# H851X.net
KiCad netlist of a schematic drawn in EAGLE
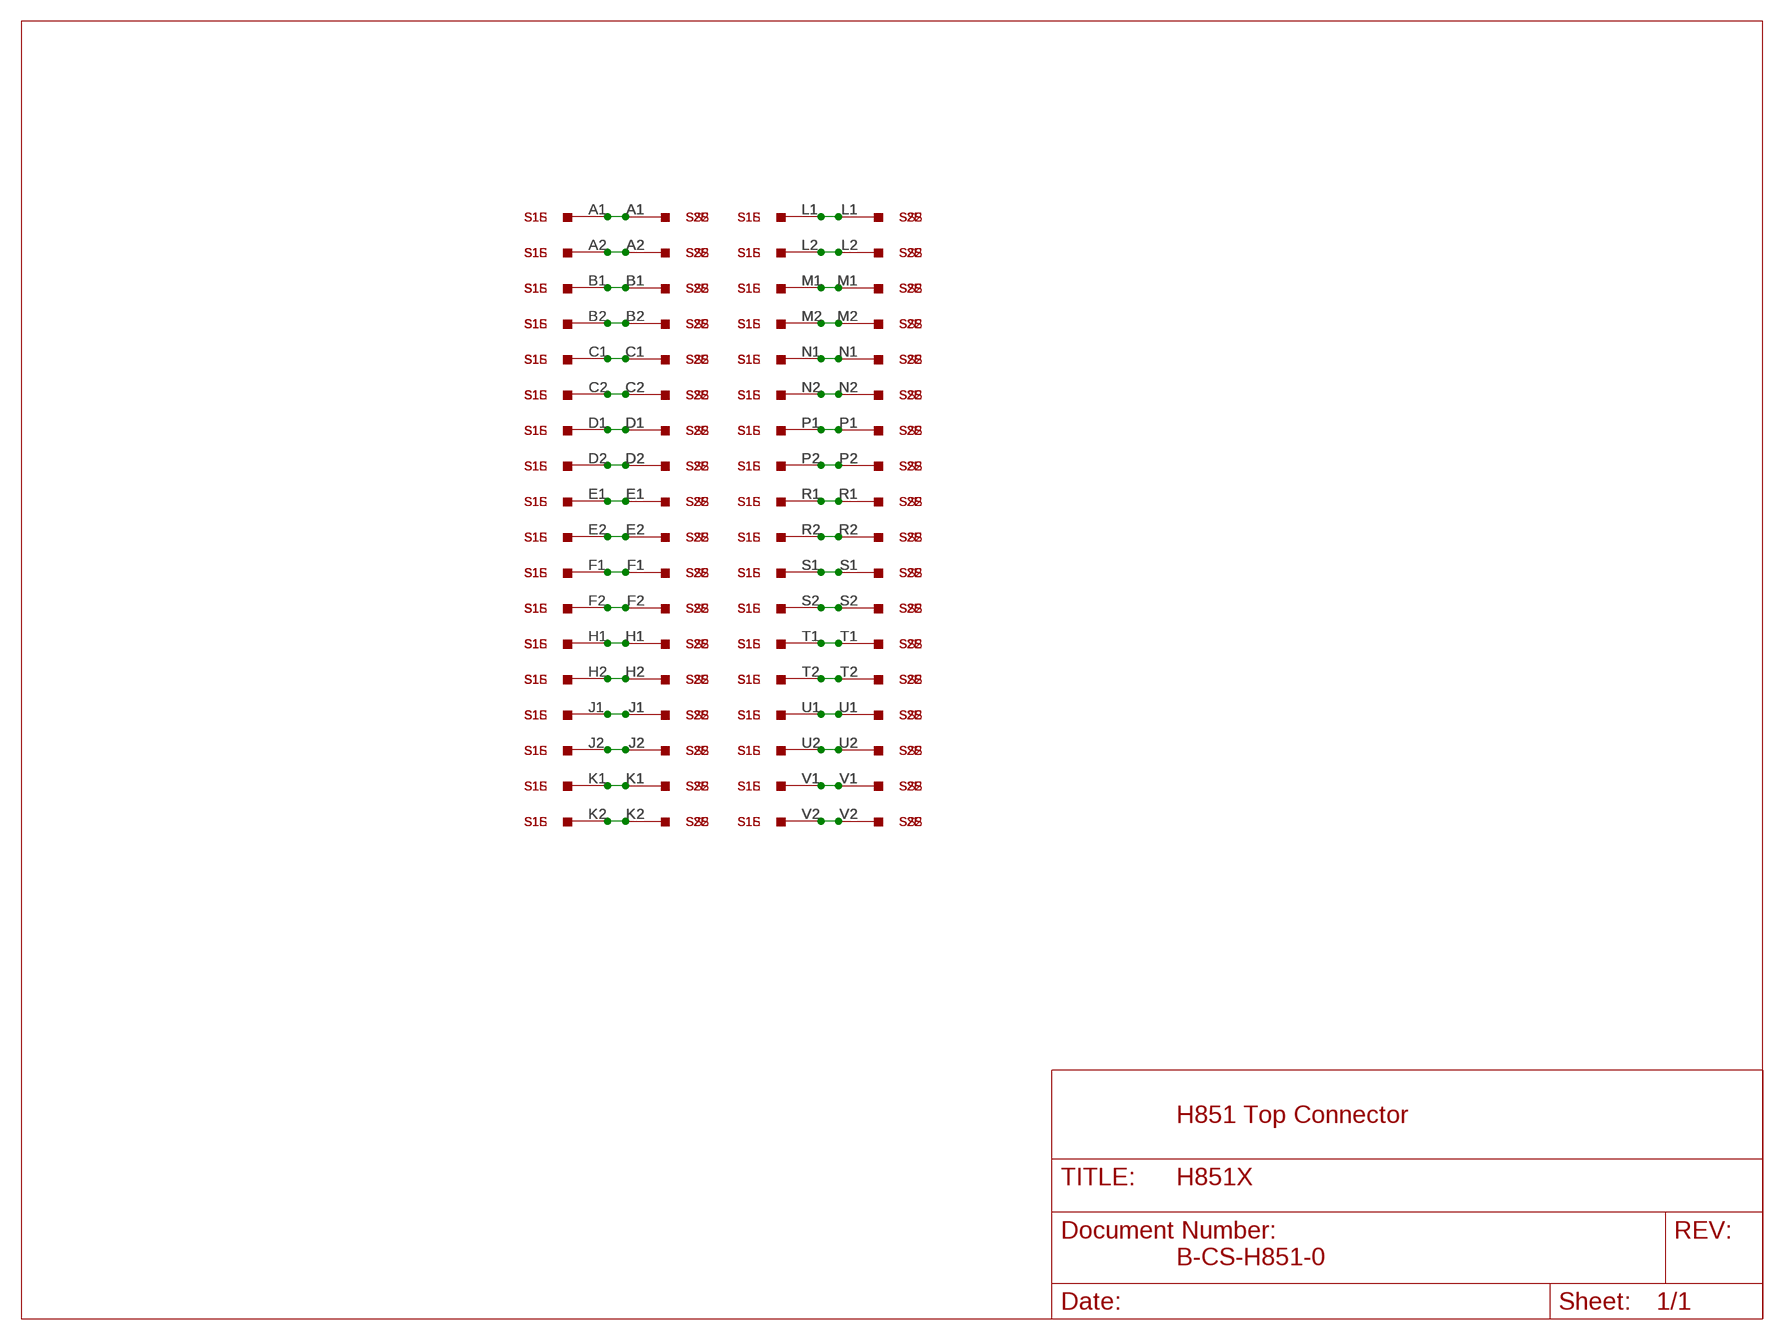
[diagram p0: schematic, sheet 1]

(export (version "E")
  (design (tool "Eeschema 10.0.6"))
  (components
    (comp (ref "S1")
      (value "M916")
      (footprint "eagle-import:H807")
      (libsource (lib "eagle-import") (part "M916"))
    )
    (comp (ref "S1E")
      (value "M916EDAC")
      (footprint "eagle-import:EDAC346-36")
      (libsource (lib "eagle-import") (part "M916EDAC"))
    )
    (comp (ref "S1S")
      (value "M916ECS")
      (footprint "eagle-import:ECS2418")
      (libsource (lib "eagle-import") (part "M916ECS"))
    )
    (comp (ref "S2")
      (value "M916")
      (footprint "eagle-import:H807")
      (libsource (lib "eagle-import") (part "M916"))
    )
    (comp (ref "S2E")
      (value "M916EDAC")
      (footprint "eagle-import:EDAC346-36")
      (libsource (lib "eagle-import") (part "M916EDAC"))
    )
    (comp (ref "S2S")
      (value "M916ECS")
      (footprint "eagle-import:ECS2418")
      (libsource (lib "eagle-import") (part "M916ECS"))
    )
  )
  (nets
    (net (code "1") (name "Net-(S1A-P$2)") (class "Default")
      (node (ref "S1") (pin "A1") (pinfunction "P$2_A1") (pintype "bidirectional"))
      (node (ref "S1E") (pin "A1") (pinfunction "P$2_A1") (pintype "bidirectional"))
      (node (ref "S1S") (pin "A1") (pinfunction "P$2_A1") (pintype "bidirectional"))
      (node (ref "S2") (pin "A1") (pinfunction "P$2_A1") (pintype "bidirectional"))
      (node (ref "S2E") (pin "A1") (pinfunction "P$2_A1") (pintype "bidirectional"))
      (node (ref "S2S") (pin "A1") (pinfunction "P$2_A1") (pintype "bidirectional"))
    )
    (net (code "2") (name "Net-(S1AA-P$2)") (class "Default")
      (node (ref "S1") (pin "R1") (pinfunction "P$2_R1") (pintype "bidirectional"))
      (node (ref "S1E") (pin "R1") (pinfunction "P$2_R1") (pintype "bidirectional"))
      (node (ref "S1S") (pin "R1") (pinfunction "P$2_R1") (pintype "bidirectional"))
      (node (ref "S2") (pin "R1") (pinfunction "P$2_R1") (pintype "bidirectional"))
      (node (ref "S2E") (pin "R1") (pinfunction "P$2_R1") (pintype "bidirectional"))
      (node (ref "S2S") (pin "R1") (pinfunction "P$2_R1") (pintype "bidirectional"))
    )
    (net (code "3") (name "Net-(S1AB-P$2)") (class "Default")
      (node (ref "S1") (pin "R2") (pinfunction "P$2_R2") (pintype "bidirectional"))
      (node (ref "S1E") (pin "R2") (pinfunction "P$2_R2") (pintype "bidirectional"))
      (node (ref "S1S") (pin "R2") (pinfunction "P$2_R2") (pintype "bidirectional"))
      (node (ref "S2") (pin "R2") (pinfunction "P$2_R2") (pintype "bidirectional"))
      (node (ref "S2E") (pin "R2") (pinfunction "P$2_R2") (pintype "bidirectional"))
      (node (ref "S2S") (pin "R2") (pinfunction "P$2_R2") (pintype "bidirectional"))
    )
    (net (code "4") (name "Net-(S1AC-P$2)") (class "Default")
      (node (ref "S1") (pin "S1") (pinfunction "P$2_S1") (pintype "bidirectional"))
      (node (ref "S1E") (pin "S1") (pinfunction "P$2_S1") (pintype "bidirectional"))
      (node (ref "S1S") (pin "S1") (pinfunction "P$2_S1") (pintype "bidirectional"))
      (node (ref "S2") (pin "S1") (pinfunction "P$2_S1") (pintype "bidirectional"))
      (node (ref "S2E") (pin "S1") (pinfunction "P$2_S1") (pintype "bidirectional"))
      (node (ref "S2S") (pin "S1") (pinfunction "P$2_S1") (pintype "bidirectional"))
    )
    (net (code "5") (name "Net-(S1AD-P$2)") (class "Default")
      (node (ref "S1") (pin "S2") (pinfunction "P$2_S2") (pintype "bidirectional"))
      (node (ref "S1E") (pin "S2") (pinfunction "P$2_S2") (pintype "bidirectional"))
      (node (ref "S1S") (pin "S2") (pinfunction "P$2_S2") (pintype "bidirectional"))
      (node (ref "S2") (pin "S2") (pinfunction "P$2_S2") (pintype "bidirectional"))
      (node (ref "S2E") (pin "S2") (pinfunction "P$2_S2") (pintype "bidirectional"))
      (node (ref "S2S") (pin "S2") (pinfunction "P$2_S2") (pintype "bidirectional"))
    )
    (net (code "6") (name "Net-(S1AE-P$2)") (class "Default")
      (node (ref "S1") (pin "T1") (pinfunction "P$2_T1") (pintype "bidirectional"))
      (node (ref "S1E") (pin "T1") (pinfunction "P$2_T1") (pintype "bidirectional"))
      (node (ref "S1S") (pin "T1") (pinfunction "P$2_T1") (pintype "bidirectional"))
      (node (ref "S2") (pin "T1") (pinfunction "P$2_T1") (pintype "bidirectional"))
      (node (ref "S2E") (pin "T1") (pinfunction "P$2_T1") (pintype "bidirectional"))
      (node (ref "S2S") (pin "T1") (pinfunction "P$2_T1") (pintype "bidirectional"))
    )
    (net (code "7") (name "Net-(S1AF-P$2)") (class "Default")
      (node (ref "S1") (pin "T2") (pinfunction "P$2_T2") (pintype "bidirectional"))
      (node (ref "S1E") (pin "T2") (pinfunction "P$2_T2") (pintype "bidirectional"))
      (node (ref "S1S") (pin "T2") (pinfunction "P$2_T2") (pintype "bidirectional"))
      (node (ref "S2") (pin "T2") (pinfunction "P$2_T2") (pintype "bidirectional"))
      (node (ref "S2E") (pin "T2") (pinfunction "P$2_T2") (pintype "bidirectional"))
      (node (ref "S2S") (pin "T2") (pinfunction "P$2_T2") (pintype "bidirectional"))
    )
    (net (code "8") (name "Net-(S1AG-P$2)") (class "Default")
      (node (ref "S1") (pin "U1") (pinfunction "P$2_U1") (pintype "bidirectional"))
      (node (ref "S1E") (pin "U1") (pinfunction "P$2_U1") (pintype "bidirectional"))
      (node (ref "S1S") (pin "U1") (pinfunction "P$2_U1") (pintype "bidirectional"))
      (node (ref "S2") (pin "U1") (pinfunction "P$2_U1") (pintype "bidirectional"))
      (node (ref "S2E") (pin "U1") (pinfunction "P$2_U1") (pintype "bidirectional"))
      (node (ref "S2S") (pin "U1") (pinfunction "P$2_U1") (pintype "bidirectional"))
    )
    (net (code "9") (name "Net-(S1AH-P$2)") (class "Default")
      (node (ref "S1") (pin "U2") (pinfunction "P$2_U2") (pintype "bidirectional"))
      (node (ref "S1E") (pin "U2") (pinfunction "P$2_U2") (pintype "bidirectional"))
      (node (ref "S1S") (pin "U2") (pinfunction "P$2_U2") (pintype "bidirectional"))
      (node (ref "S2") (pin "U2") (pinfunction "P$2_U2") (pintype "bidirectional"))
      (node (ref "S2E") (pin "U2") (pinfunction "P$2_U2") (pintype "bidirectional"))
      (node (ref "S2S") (pin "U2") (pinfunction "P$2_U2") (pintype "bidirectional"))
    )
    (net (code "10") (name "Net-(S1AI-P$2)") (class "Default")
      (node (ref "S1") (pin "V1") (pinfunction "P$2_V1") (pintype "bidirectional"))
      (node (ref "S1E") (pin "V1") (pinfunction "P$2_V1") (pintype "bidirectional"))
      (node (ref "S1S") (pin "V1") (pinfunction "P$2_V1") (pintype "bidirectional"))
      (node (ref "S2") (pin "V1") (pinfunction "P$2_V1") (pintype "bidirectional"))
      (node (ref "S2E") (pin "V1") (pinfunction "P$2_V1") (pintype "bidirectional"))
      (node (ref "S2S") (pin "V1") (pinfunction "P$2_V1") (pintype "bidirectional"))
    )
    (net (code "11") (name "Net-(S1AJ-P$2)") (class "Default")
      (node (ref "S1") (pin "V2") (pinfunction "P$2_V2") (pintype "bidirectional"))
      (node (ref "S1E") (pin "V2") (pinfunction "P$2_V2") (pintype "bidirectional"))
      (node (ref "S1S") (pin "V2") (pinfunction "P$2_V2") (pintype "bidirectional"))
      (node (ref "S2") (pin "V2") (pinfunction "P$2_V2") (pintype "bidirectional"))
      (node (ref "S2E") (pin "V2") (pinfunction "P$2_V2") (pintype "bidirectional"))
      (node (ref "S2S") (pin "V2") (pinfunction "P$2_V2") (pintype "bidirectional"))
    )
    (net (code "12") (name "Net-(S1B-P$2)") (class "Default")
      (node (ref "S1") (pin "A2") (pinfunction "P$2_A2") (pintype "bidirectional"))
      (node (ref "S1E") (pin "A2") (pinfunction "P$2_A2") (pintype "bidirectional"))
      (node (ref "S1S") (pin "A2") (pinfunction "P$2_A2") (pintype "bidirectional"))
      (node (ref "S2") (pin "A2") (pinfunction "P$2_A2") (pintype "bidirectional"))
      (node (ref "S2E") (pin "A2") (pinfunction "P$2_A2") (pintype "bidirectional"))
      (node (ref "S2S") (pin "A2") (pinfunction "P$2_A2") (pintype "bidirectional"))
    )
    (net (code "13") (name "Net-(S1C-P$2)") (class "Default")
      (node (ref "S1") (pin "B1") (pinfunction "P$2_B1") (pintype "bidirectional"))
      (node (ref "S1E") (pin "B1") (pinfunction "P$2_B1") (pintype "bidirectional"))
      (node (ref "S1S") (pin "B1") (pinfunction "P$2_B1") (pintype "bidirectional"))
      (node (ref "S2") (pin "B1") (pinfunction "P$2_B1") (pintype "bidirectional"))
      (node (ref "S2E") (pin "B1") (pinfunction "P$2_B1") (pintype "bidirectional"))
      (node (ref "S2S") (pin "B1") (pinfunction "P$2_B1") (pintype "bidirectional"))
    )
    (net (code "14") (name "Net-(S1D-P$2)") (class "Default")
      (node (ref "S1") (pin "B2") (pinfunction "P$2_B2") (pintype "bidirectional"))
      (node (ref "S1E") (pin "B2") (pinfunction "P$2_B2") (pintype "bidirectional"))
      (node (ref "S1S") (pin "B2") (pinfunction "P$2_B2") (pintype "bidirectional"))
      (node (ref "S2") (pin "B2") (pinfunction "P$2_B2") (pintype "bidirectional"))
      (node (ref "S2E") (pin "B2") (pinfunction "P$2_B2") (pintype "bidirectional"))
      (node (ref "S2S") (pin "B2") (pinfunction "P$2_B2") (pintype "bidirectional"))
    )
    (net (code "15") (name "Net-(S1E-P$2)") (class "Default")
      (node (ref "S1") (pin "C1") (pinfunction "P$2_C1") (pintype "bidirectional"))
      (node (ref "S1E") (pin "C1") (pinfunction "P$2_C1") (pintype "bidirectional"))
      (node (ref "S1S") (pin "C1") (pinfunction "P$2_C1") (pintype "bidirectional"))
      (node (ref "S2") (pin "C1") (pinfunction "P$2_C1") (pintype "bidirectional"))
      (node (ref "S2E") (pin "C1") (pinfunction "P$2_C1") (pintype "bidirectional"))
      (node (ref "S2S") (pin "C1") (pinfunction "P$2_C1") (pintype "bidirectional"))
    )
    (net (code "16") (name "Net-(S1EF-P$2)") (class "Default")
      (node (ref "S1") (pin "C2") (pinfunction "P$2_C2") (pintype "bidirectional"))
      (node (ref "S1E") (pin "C2") (pinfunction "P$2_C2") (pintype "bidirectional"))
      (node (ref "S1S") (pin "C2") (pinfunction "P$2_C2") (pintype "bidirectional"))
      (node (ref "S2") (pin "C2") (pinfunction "P$2_C2") (pintype "bidirectional"))
      (node (ref "S2E") (pin "C2") (pinfunction "P$2_C2") (pintype "bidirectional"))
      (node (ref "S2S") (pin "C2") (pinfunction "P$2_C2") (pintype "bidirectional"))
    )
    (net (code "17") (name "Net-(S1EG-P$2)") (class "Default")
      (node (ref "S1") (pin "D1") (pinfunction "P$2_D1") (pintype "bidirectional"))
      (node (ref "S1E") (pin "D1") (pinfunction "P$2_D1") (pintype "bidirectional"))
      (node (ref "S1S") (pin "D1") (pinfunction "P$2_D1") (pintype "bidirectional"))
      (node (ref "S2") (pin "D1") (pinfunction "P$2_D1") (pintype "bidirectional"))
      (node (ref "S2E") (pin "D1") (pinfunction "P$2_D1") (pintype "bidirectional"))
      (node (ref "S2S") (pin "D1") (pinfunction "P$2_D1") (pintype "bidirectional"))
    )
    (net (code "18") (name "Net-(S1EH-P$2)") (class "Default")
      (node (ref "S1") (pin "D2") (pinfunction "P$2_D2") (pintype "bidirectional"))
      (node (ref "S1E") (pin "D2") (pinfunction "P$2_D2") (pintype "bidirectional"))
      (node (ref "S1S") (pin "D2") (pinfunction "P$2_D2") (pintype "bidirectional"))
      (node (ref "S2") (pin "D2") (pinfunction "P$2_D2") (pintype "bidirectional"))
      (node (ref "S2E") (pin "D2") (pinfunction "P$2_D2") (pintype "bidirectional"))
      (node (ref "S2S") (pin "D2") (pinfunction "P$2_D2") (pintype "bidirectional"))
    )
    (net (code "19") (name "Net-(S1EI-P$2)") (class "Default")
      (node (ref "S1") (pin "E1") (pinfunction "P$2_E1") (pintype "bidirectional"))
      (node (ref "S1E") (pin "E1") (pinfunction "P$2_E1") (pintype "bidirectional"))
      (node (ref "S1S") (pin "E1") (pinfunction "P$2_E1") (pintype "bidirectional"))
      (node (ref "S2") (pin "E1") (pinfunction "P$2_E1") (pintype "bidirectional"))
      (node (ref "S2E") (pin "E1") (pinfunction "P$2_E1") (pintype "bidirectional"))
      (node (ref "S2S") (pin "E1") (pinfunction "P$2_E1") (pintype "bidirectional"))
    )
    (net (code "20") (name "Net-(S1EJ-P$2)") (class "Default")
      (node (ref "S1") (pin "E2") (pinfunction "P$2_E2") (pintype "bidirectional"))
      (node (ref "S1E") (pin "E2") (pinfunction "P$2_E2") (pintype "bidirectional"))
      (node (ref "S1S") (pin "E2") (pinfunction "P$2_E2") (pintype "bidirectional"))
      (node (ref "S2") (pin "E2") (pinfunction "P$2_E2") (pintype "bidirectional"))
      (node (ref "S2E") (pin "E2") (pinfunction "P$2_E2") (pintype "bidirectional"))
      (node (ref "S2S") (pin "E2") (pinfunction "P$2_E2") (pintype "bidirectional"))
    )
    (net (code "21") (name "Net-(S1EK-P$2)") (class "Default")
      (node (ref "S1") (pin "F1") (pinfunction "P$2_F1") (pintype "bidirectional"))
      (node (ref "S1E") (pin "F1") (pinfunction "P$2_F1") (pintype "bidirectional"))
      (node (ref "S1S") (pin "F1") (pinfunction "P$2_F1") (pintype "bidirectional"))
      (node (ref "S2") (pin "F1") (pinfunction "P$2_F1") (pintype "bidirectional"))
      (node (ref "S2E") (pin "F1") (pinfunction "P$2_F1") (pintype "bidirectional"))
      (node (ref "S2S") (pin "F1") (pinfunction "P$2_F1") (pintype "bidirectional"))
    )
    (net (code "22") (name "Net-(S1EL-P$2)") (class "Default")
      (node (ref "S1") (pin "F2") (pinfunction "P$2_F2") (pintype "bidirectional"))
      (node (ref "S1E") (pin "F2") (pinfunction "P$2_F2") (pintype "bidirectional"))
      (node (ref "S1S") (pin "F2") (pinfunction "P$2_F2") (pintype "bidirectional"))
      (node (ref "S2") (pin "F2") (pinfunction "P$2_F2") (pintype "bidirectional"))
      (node (ref "S2E") (pin "F2") (pinfunction "P$2_F2") (pintype "bidirectional"))
      (node (ref "S2S") (pin "F2") (pinfunction "P$2_F2") (pintype "bidirectional"))
    )
    (net (code "23") (name "Net-(S1EM-P$2)") (class "Default")
      (node (ref "S1") (pin "H1") (pinfunction "P$2_H1") (pintype "bidirectional"))
      (node (ref "S1E") (pin "H1") (pinfunction "P$2_H1") (pintype "bidirectional"))
      (node (ref "S1S") (pin "H1") (pinfunction "P$2_H1") (pintype "bidirectional"))
      (node (ref "S2") (pin "H1") (pinfunction "P$2_H1") (pintype "bidirectional"))
      (node (ref "S2E") (pin "H1") (pinfunction "P$2_H1") (pintype "bidirectional"))
      (node (ref "S2S") (pin "H1") (pinfunction "P$2_H1") (pintype "bidirectional"))
    )
    (net (code "24") (name "Net-(S1EN-P$2)") (class "Default")
      (node (ref "S1") (pin "H2") (pinfunction "P$2_H2") (pintype "bidirectional"))
      (node (ref "S1E") (pin "H2") (pinfunction "P$2_H2") (pintype "bidirectional"))
      (node (ref "S1S") (pin "H2") (pinfunction "P$2_H2") (pintype "bidirectional"))
      (node (ref "S2") (pin "H2") (pinfunction "P$2_H2") (pintype "bidirectional"))
      (node (ref "S2E") (pin "H2") (pinfunction "P$2_H2") (pintype "bidirectional"))
      (node (ref "S2S") (pin "H2") (pinfunction "P$2_H2") (pintype "bidirectional"))
    )
    (net (code "25") (name "Net-(S1EO-P$2)") (class "Default")
      (node (ref "S1") (pin "J1") (pinfunction "P$2_J1") (pintype "bidirectional"))
      (node (ref "S1E") (pin "J1") (pinfunction "P$2_J1") (pintype "bidirectional"))
      (node (ref "S1S") (pin "J1") (pinfunction "P$2_J1") (pintype "bidirectional"))
      (node (ref "S2") (pin "J1") (pinfunction "P$2_J1") (pintype "bidirectional"))
      (node (ref "S2E") (pin "J1") (pinfunction "P$2_J1") (pintype "bidirectional"))
      (node (ref "S2S") (pin "J1") (pinfunction "P$2_J1") (pintype "bidirectional"))
    )
    (net (code "26") (name "Net-(S1EP-P$2)") (class "Default")
      (node (ref "S1") (pin "J2") (pinfunction "P$2_J2") (pintype "bidirectional"))
      (node (ref "S1E") (pin "J2") (pinfunction "P$2_J2") (pintype "bidirectional"))
      (node (ref "S1S") (pin "J2") (pinfunction "P$2_J2") (pintype "bidirectional"))
      (node (ref "S2") (pin "J2") (pinfunction "P$2_J2") (pintype "bidirectional"))
      (node (ref "S2E") (pin "J2") (pinfunction "P$2_J2") (pintype "bidirectional"))
      (node (ref "S2S") (pin "J2") (pinfunction "P$2_J2") (pintype "bidirectional"))
    )
    (net (code "27") (name "Net-(S1EQ-P$2)") (class "Default")
      (node (ref "S1") (pin "K1") (pinfunction "P$2_K1") (pintype "bidirectional"))
      (node (ref "S1E") (pin "K1") (pinfunction "P$2_K1") (pintype "bidirectional"))
      (node (ref "S1S") (pin "K1") (pinfunction "P$2_K1") (pintype "bidirectional"))
      (node (ref "S2") (pin "K1") (pinfunction "P$2_K1") (pintype "bidirectional"))
      (node (ref "S2E") (pin "K1") (pinfunction "P$2_K1") (pintype "bidirectional"))
      (node (ref "S2S") (pin "K1") (pinfunction "P$2_K1") (pintype "bidirectional"))
    )
    (net (code "28") (name "Net-(S1ER-P$2)") (class "Default")
      (node (ref "S1") (pin "K2") (pinfunction "P$2_K2") (pintype "bidirectional"))
      (node (ref "S1E") (pin "K2") (pinfunction "P$2_K2") (pintype "bidirectional"))
      (node (ref "S1S") (pin "K2") (pinfunction "P$2_K2") (pintype "bidirectional"))
      (node (ref "S2") (pin "K2") (pinfunction "P$2_K2") (pintype "bidirectional"))
      (node (ref "S2E") (pin "K2") (pinfunction "P$2_K2") (pintype "bidirectional"))
      (node (ref "S2S") (pin "K2") (pinfunction "P$2_K2") (pintype "bidirectional"))
    )
    (net (code "29") (name "Net-(S1ES-P$2)") (class "Default")
      (node (ref "S1") (pin "L1") (pinfunction "P$2_L1") (pintype "bidirectional"))
      (node (ref "S1E") (pin "L1") (pinfunction "P$2_L1") (pintype "bidirectional"))
      (node (ref "S1S") (pin "L1") (pinfunction "P$2_L1") (pintype "bidirectional"))
      (node (ref "S2") (pin "L1") (pinfunction "P$2_L1") (pintype "bidirectional"))
      (node (ref "S2E") (pin "L1") (pinfunction "P$2_L1") (pintype "bidirectional"))
      (node (ref "S2S") (pin "L1") (pinfunction "P$2_L1") (pintype "bidirectional"))
    )
    (net (code "30") (name "Net-(S1ET-P$2)") (class "Default")
      (node (ref "S1") (pin "L2") (pinfunction "P$2_L2") (pintype "bidirectional"))
      (node (ref "S1E") (pin "L2") (pinfunction "P$2_L2") (pintype "bidirectional"))
      (node (ref "S1S") (pin "L2") (pinfunction "P$2_L2") (pintype "bidirectional"))
      (node (ref "S2") (pin "L2") (pinfunction "P$2_L2") (pintype "bidirectional"))
      (node (ref "S2E") (pin "L2") (pinfunction "P$2_L2") (pintype "bidirectional"))
      (node (ref "S2S") (pin "L2") (pinfunction "P$2_L2") (pintype "bidirectional"))
    )
    (net (code "31") (name "Net-(S1EU-P$2)") (class "Default")
      (node (ref "S1") (pin "M1") (pinfunction "P$2_M1") (pintype "bidirectional"))
      (node (ref "S1E") (pin "M1") (pinfunction "P$2_M1") (pintype "bidirectional"))
      (node (ref "S1S") (pin "M1") (pinfunction "P$2_M1") (pintype "bidirectional"))
      (node (ref "S2") (pin "M1") (pinfunction "P$2_M1") (pintype "bidirectional"))
      (node (ref "S2E") (pin "M1") (pinfunction "P$2_M1") (pintype "bidirectional"))
      (node (ref "S2S") (pin "M1") (pinfunction "P$2_M1") (pintype "bidirectional"))
    )
    (net (code "32") (name "Net-(S1EV-P$2)") (class "Default")
      (node (ref "S1") (pin "M2") (pinfunction "P$2_M2") (pintype "bidirectional"))
      (node (ref "S1E") (pin "M2") (pinfunction "P$2_M2") (pintype "bidirectional"))
      (node (ref "S1S") (pin "M2") (pinfunction "P$2_M2") (pintype "bidirectional"))
      (node (ref "S2") (pin "M2") (pinfunction "P$2_M2") (pintype "bidirectional"))
      (node (ref "S2E") (pin "M2") (pinfunction "P$2_M2") (pintype "bidirectional"))
      (node (ref "S2S") (pin "M2") (pinfunction "P$2_M2") (pintype "bidirectional"))
    )
    (net (code "33") (name "Net-(S1EW-P$2)") (class "Default")
      (node (ref "S1") (pin "N1") (pinfunction "P$2_N1") (pintype "bidirectional"))
      (node (ref "S1E") (pin "N1") (pinfunction "P$2_N1") (pintype "bidirectional"))
      (node (ref "S1S") (pin "N1") (pinfunction "P$2_N1") (pintype "bidirectional"))
      (node (ref "S2") (pin "N1") (pinfunction "P$2_N1") (pintype "bidirectional"))
      (node (ref "S2E") (pin "N1") (pinfunction "P$2_N1") (pintype "bidirectional"))
      (node (ref "S2S") (pin "N1") (pinfunction "P$2_N1") (pintype "bidirectional"))
    )
    (net (code "34") (name "Net-(S1EX-P$2)") (class "Default")
      (node (ref "S1") (pin "N2") (pinfunction "P$2_N2") (pintype "bidirectional"))
      (node (ref "S1E") (pin "N2") (pinfunction "P$2_N2") (pintype "bidirectional"))
      (node (ref "S1S") (pin "N2") (pinfunction "P$2_N2") (pintype "bidirectional"))
      (node (ref "S2") (pin "N2") (pinfunction "P$2_N2") (pintype "bidirectional"))
      (node (ref "S2E") (pin "N2") (pinfunction "P$2_N2") (pintype "bidirectional"))
      (node (ref "S2S") (pin "N2") (pinfunction "P$2_N2") (pintype "bidirectional"))
    )
    (net (code "35") (name "Net-(S1EY-P$2)") (class "Default")
      (node (ref "S1") (pin "P1") (pinfunction "P$2_P1") (pintype "bidirectional"))
      (node (ref "S1E") (pin "P1") (pinfunction "P$2_P1") (pintype "bidirectional"))
      (node (ref "S1S") (pin "P1") (pinfunction "P$2_P1") (pintype "bidirectional"))
      (node (ref "S2") (pin "P1") (pinfunction "P$2_P1") (pintype "bidirectional"))
      (node (ref "S2E") (pin "P1") (pinfunction "P$2_P1") (pintype "bidirectional"))
      (node (ref "S2S") (pin "P1") (pinfunction "P$2_P1") (pintype "bidirectional"))
    )
    (net (code "36") (name "Net-(S1EZ-P$2)") (class "Default")
      (node (ref "S1") (pin "P2") (pinfunction "P$2_P2") (pintype "bidirectional"))
      (node (ref "S1E") (pin "P2") (pinfunction "P$2_P2") (pintype "bidirectional"))
      (node (ref "S1S") (pin "P2") (pinfunction "P$2_P2") (pintype "bidirectional"))
      (node (ref "S2") (pin "P2") (pinfunction "P$2_P2") (pintype "bidirectional"))
      (node (ref "S2E") (pin "P2") (pinfunction "P$2_P2") (pintype "bidirectional"))
      (node (ref "S2S") (pin "P2") (pinfunction "P$2_P2") (pintype "bidirectional"))
    )
  )
)
